# 2_STM32F334R8T6Board_Display_WIFI.net
KiCad netlist of a schematic drawn in Altium Designer
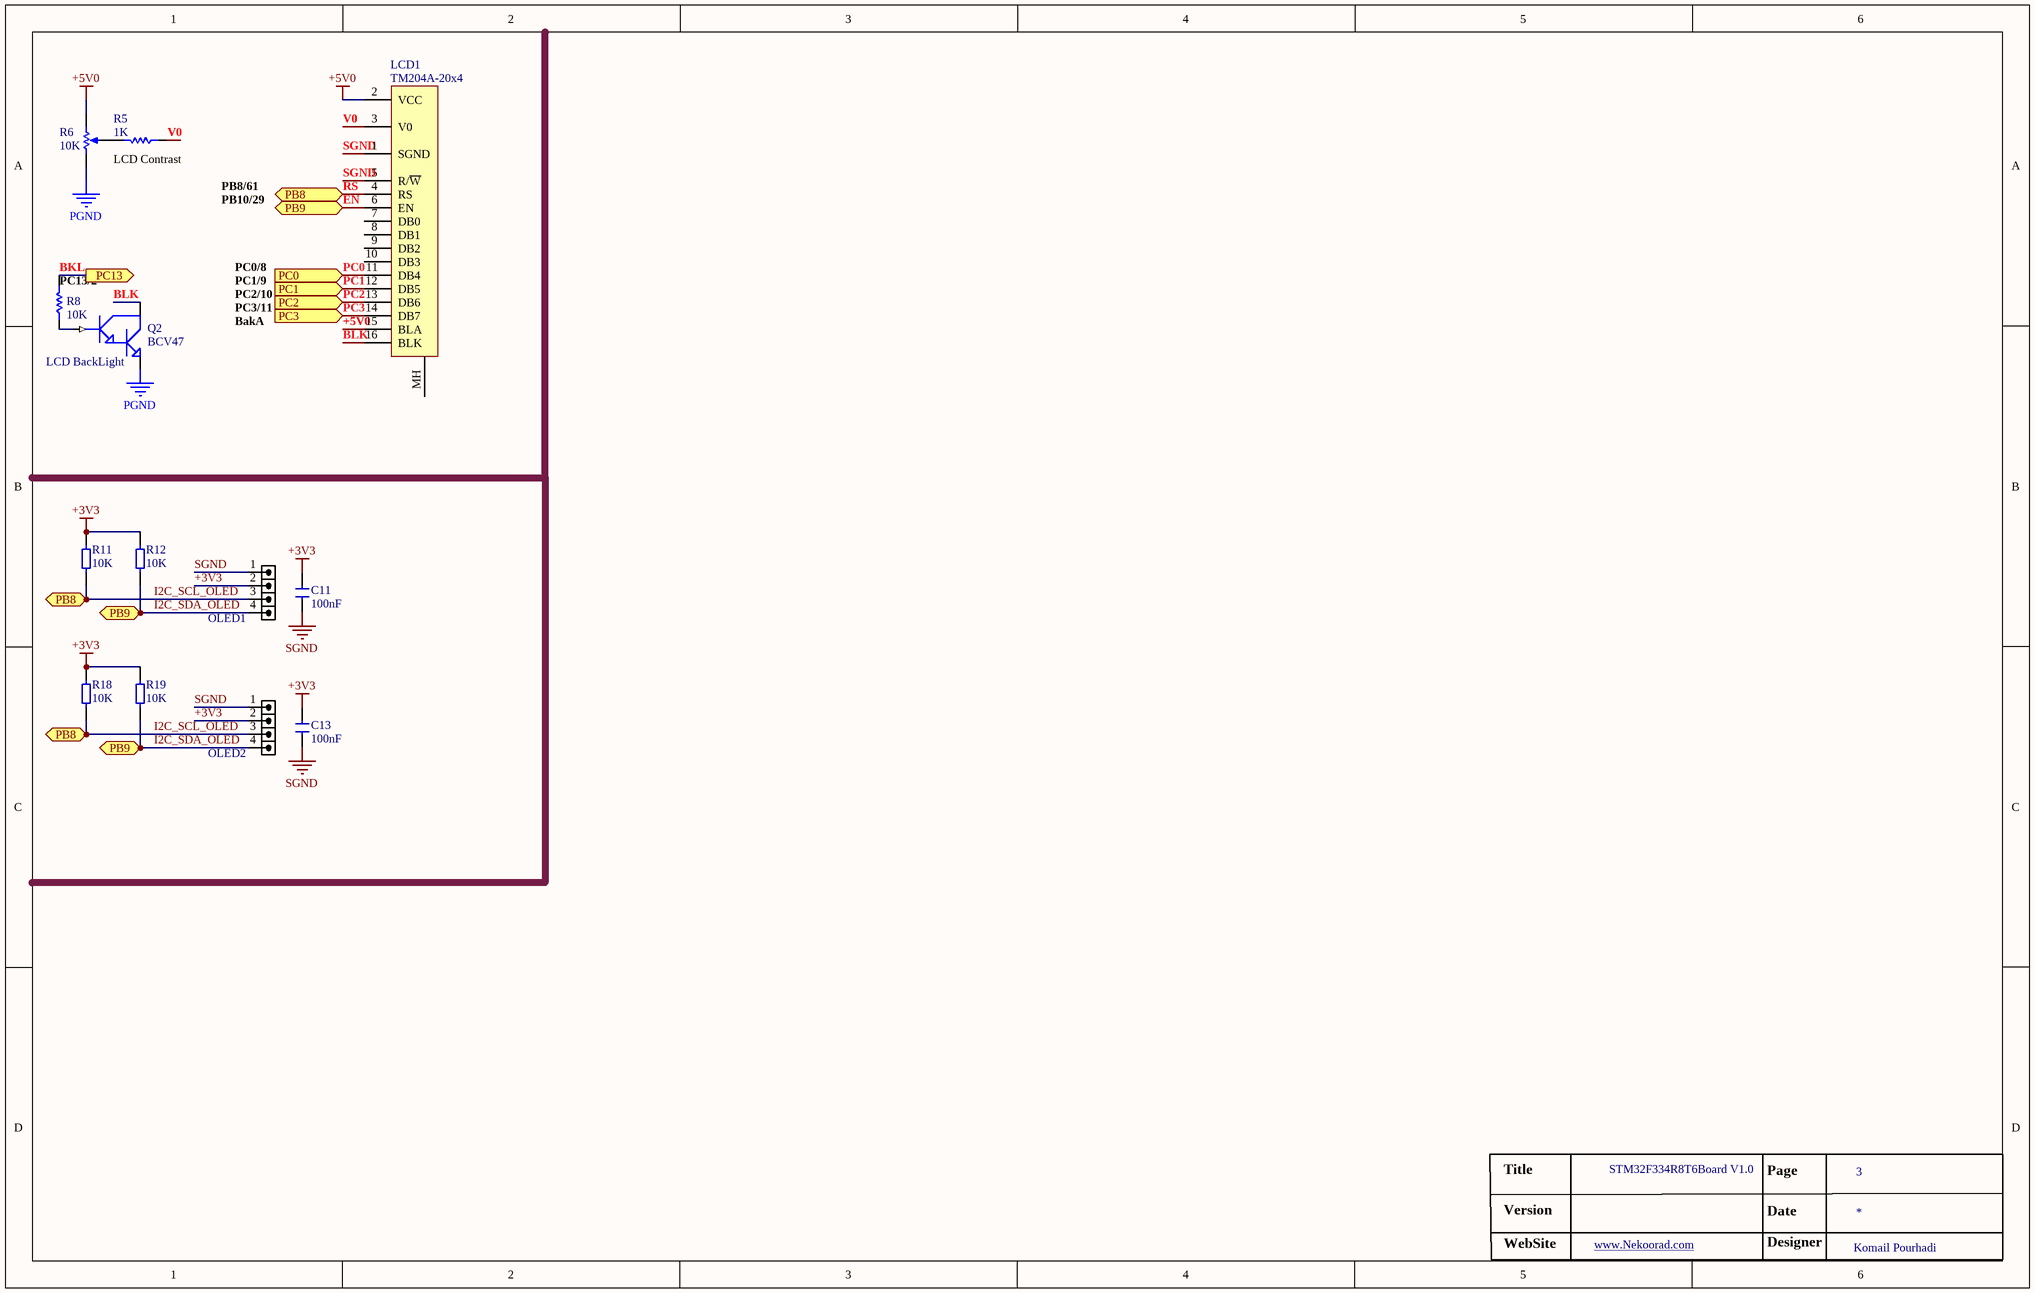
[diagram p0: [2]STM32F334R8T6Board_Display_WIFI.SchDoc]

(export (version "E")
  (design (tool "Eeschema 10.0.6"))
  (components
    (comp (ref "C11")
      (value "Capacitor SMD")
      (footprint "SMD_CAP_1206")
      (fields (field (name "ALTIUM_UNNAMED_1") "100nF"))
      (libsource (lib "ZetaBoard_Lib") (part "Capacitor SMD"))
    )
    (comp (ref "C13")
      (value "Capacitor SMD")
      (footprint "SMD_CAP_1206")
      (fields (field (name "ALTIUM_UNNAMED_1") "100nF"))
      (libsource (lib "ZetaBoard_Lib") (part "Capacitor SMD"))
    )
    (comp (ref "LCD1")
      (value "TM204A-20x4")
      (footprint "HDR1X16")
      (fields (field (name "DESIGNER") "Saeid Jorablo"))
      (libsource (lib "My Library") (part "LCD"))
    )
    (comp (ref "OLED1")
      (value "HDR1X4")
      (footprint "HDR1X4")
      (description "CONN, HEADER, Male, pitch: 2.54mm, 4POS")
      (libsource (lib "conn_header") (part "HDR_M_1X4"))
    )
    (comp (ref "OLED2")
      (value "HDR1X4")
      (footprint "HDR1X4")
      (description "CONN, HEADER, Male, pitch: 2.54mm, 4POS")
      (libsource (lib "conn_header") (part "HDR_M_1X4"))
    )
    (comp (ref "Q2")
      (value "BCV47")
      (footprint "SOT23_BEC_M")
      (libsource (lib "MyAltiumLib") (part "NPN DAR"))
    )
    (comp (ref "R5")
      (value "1K")
      (footprint "RES_1206")
      (description "Resistor")
      (fields (field (name "TOLERANCE") "5%") (field (name "POWER") "1/8 W"))
      (libsource (lib "My Library") (part "Resistor"))
    )
    (comp (ref "R6")
      (value "10K")
      (footprint "JFP")
      (description "Potentiometer")
      (fields (field (name "Comment") "RPot") (field (name "PUBLISHER") "Altium Limited"))
      (libsource (lib "Miscellaneous Devices") (part "RPot"))
    )
    (comp (ref "R8")
      (value "10K")
      (footprint "RES_1206")
      (description "Resistor")
      (fields (field (name "TOLERANCE") "5%") (field (name "POWER") "1/8 W"))
      (libsource (lib "My Library") (part "Resistor"))
    )
    (comp (ref "R11")
      (value "RESISTOR")
      (footprint "RES_1206")
      (fields (field (name "ALTIUM_UNNAMED_1") "10K"))
      (libsource (lib "ZetaBoard_Lib") (part "Resistor SMD"))
    )
    (comp (ref "R12")
      (value "RESISTOR")
      (footprint "RES_1206")
      (fields (field (name "ALTIUM_UNNAMED_1") "10K"))
      (libsource (lib "ZetaBoard_Lib") (part "Resistor SMD"))
    )
    (comp (ref "R18")
      (value "RESISTOR")
      (footprint "RES_1206")
      (fields (field (name "ALTIUM_UNNAMED_1") "10K"))
      (libsource (lib "ZetaBoard_Lib") (part "Resistor SMD"))
    )
    (comp (ref "R19")
      (value "RESISTOR")
      (footprint "RES_1206")
      (fields (field (name "ALTIUM_UNNAMED_1") "10K"))
      (libsource (lib "ZetaBoard_Lib") (part "Resistor SMD"))
    )
  )
  (nets
    (net (code "1") (name "+3V3") (class "Default")
      (node (ref "C11") (pin "2") (pintype "passive"))
      (node (ref "C13") (pin "2") (pintype "passive"))
      (node (ref "OLED1") (pin "2") (pinfunction "2_2") (pintype "passive"))
      (node (ref "OLED2") (pin "2") (pinfunction "2_2") (pintype "passive"))
      (node (ref "R11") (pin "1") (pintype "passive"))
      (node (ref "R12") (pin "1") (pintype "passive"))
      (node (ref "R18") (pin "1") (pintype "passive"))
      (node (ref "R19") (pin "1") (pintype "passive"))
    )
    (net (code "2") (name "+5V0") (class "Default")
      (node (ref "LCD1") (pin "15") (pinfunction "BLA_15") (pintype "passive"))
      (node (ref "LCD1") (pin "2") (pinfunction "VCC_2") (pintype "passive"))
      (node (ref "R6") (pin "3") (pinfunction "BOT_3") (pintype "passive"))
    )
    (net (code "3") (name "/BKL") (class "Default")
      (node (ref "R8") (pin "2") (pinfunction "2_2") (pintype "passive"))
    )
    (net (code "4") (name "/BLK") (class "Default")
      (node (ref "LCD1") (pin "16") (pinfunction "BLK_16") (pintype "passive"))
      (node (ref "Q2") (pin "3") (pinfunction "C_3") (pintype "passive"))
    )
    (net (code "5") (name "/EN") (class "Default")
      (node (ref "LCD1") (pin "6") (pinfunction "EN_6") (pintype "passive"))
      (node (ref "OLED1") (pin "4") (pinfunction "4_4") (pintype "passive"))
      (node (ref "OLED2") (pin "4") (pinfunction "4_4") (pintype "passive"))
      (node (ref "R12") (pin "2") (pintype "passive"))
      (node (ref "R19") (pin "2") (pintype "passive"))
    )
    (net (code "6") (name "/I2C_SCL_OLED") (class "Default")
      (node (ref "LCD1") (pin "4") (pinfunction "RS_4") (pintype "passive"))
      (node (ref "OLED1") (pin "3") (pinfunction "3_3") (pintype "passive"))
      (node (ref "OLED2") (pin "3") (pinfunction "3_3") (pintype "passive"))
      (node (ref "R11") (pin "2") (pintype "passive"))
      (node (ref "R18") (pin "2") (pintype "passive"))
    )
    (net (code "7") (name "/PC0") (class "Default")
      (node (ref "LCD1") (pin "11") (pinfunction "DB4_11") (pintype "passive"))
    )
    (net (code "8") (name "/PC1") (class "Default")
      (node (ref "LCD1") (pin "12") (pinfunction "DB5_12") (pintype "passive"))
    )
    (net (code "9") (name "/PC2") (class "Default")
      (node (ref "LCD1") (pin "13") (pinfunction "DB6_13") (pintype "passive"))
    )
    (net (code "10") (name "/PC3") (class "Default")
      (node (ref "LCD1") (pin "14") (pinfunction "DB7_14") (pintype "passive"))
    )
    (net (code "11") (name "/V0") (class "Default")
      (node (ref "LCD1") (pin "3") (pinfunction "V0_3") (pintype "passive"))
      (node (ref "R5") (pin "1") (pinfunction "1_1") (pintype "passive"))
    )
    (net (code "12") (name "Net-(Q2-B)") (class "Default")
      (node (ref "Q2") (pin "1") (pinfunction "B_1") (pintype "input"))
      (node (ref "R8") (pin "1") (pinfunction "1_1") (pintype "passive"))
    )
    (net (code "13") (name "Net-(R6-TAP)") (class "Default")
      (node (ref "R5") (pin "2") (pinfunction "2_2") (pintype "passive"))
      (node (ref "R6") (pin "2") (pinfunction "TAP_2") (pintype "passive"))
    )
    (net (code "14") (name "PGND") (class "Default")
      (node (ref "Q2") (pin "2") (pinfunction "E_2") (pintype "passive"))
      (node (ref "R6") (pin "1") (pinfunction "TOP_1") (pintype "passive"))
    )
    (net (code "15") (name "SGND") (class "Default")
      (node (ref "C11") (pin "1") (pintype "passive"))
      (node (ref "C13") (pin "1") (pintype "passive"))
      (node (ref "LCD1") (pin "1") (pinfunction "SGND_1") (pintype "passive"))
      (node (ref "LCD1") (pin "5") (pinfunction "R/~{W}_5") (pintype "passive"))
      (node (ref "OLED1") (pin "1") (pinfunction "1_1") (pintype "passive"))
      (node (ref "OLED2") (pin "1") (pinfunction "1_1") (pintype "passive"))
    )
    (net (code "16") (name "unconnected-(LCD1-DB0-Pad7)") (class "Default")
      (node (ref "LCD1") (pin "7") (pinfunction "DB0_7") (pintype "passive"))
    )
    (net (code "17") (name "unconnected-(LCD1-DB1-Pad8)") (class "Default")
      (node (ref "LCD1") (pin "8") (pinfunction "DB1_8") (pintype "passive"))
    )
    (net (code "18") (name "unconnected-(LCD1-DB2-Pad9)") (class "Default")
      (node (ref "LCD1") (pin "9") (pinfunction "DB2_9") (pintype "passive"))
    )
    (net (code "19") (name "unconnected-(LCD1-DB3-Pad10)") (class "Default")
      (node (ref "LCD1") (pin "10") (pinfunction "DB3_10") (pintype "passive"))
    )
    (net (code "20") (name "unconnected-(LCD1-PadMH)") (class "Default")
      (node (ref "LCD1") (pin "MH") (pinfunction "MH_MH") (pintype "passive"))
    )
  )
)
